# ESP32boardforCNCFTDI.net
KiCad netlist of a schematic drawn in EAGLE
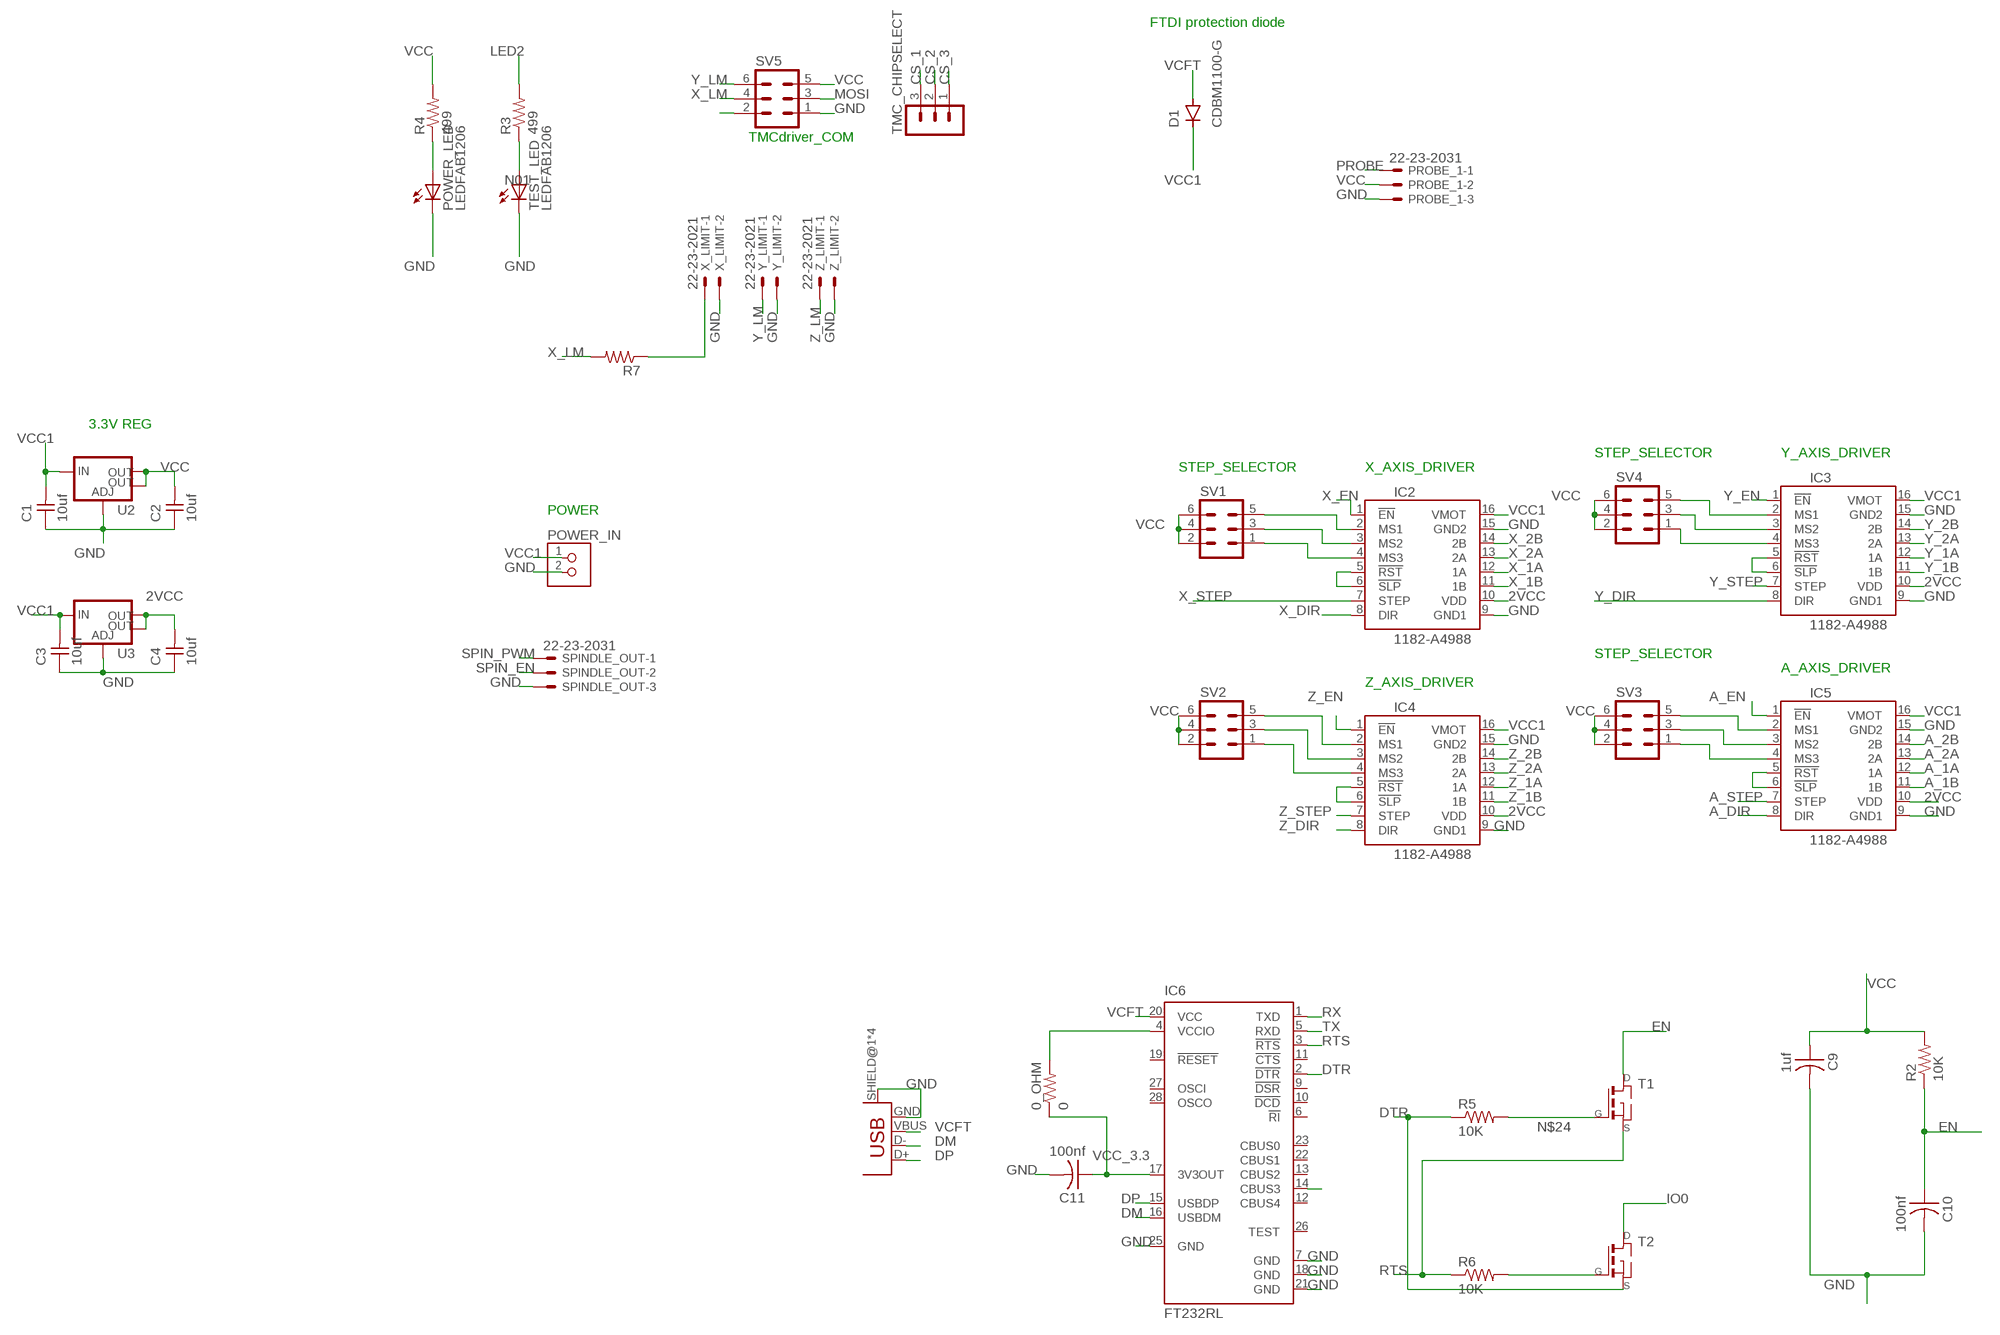
[diagram p0: schematic, sheet 1, part 1 of 2]
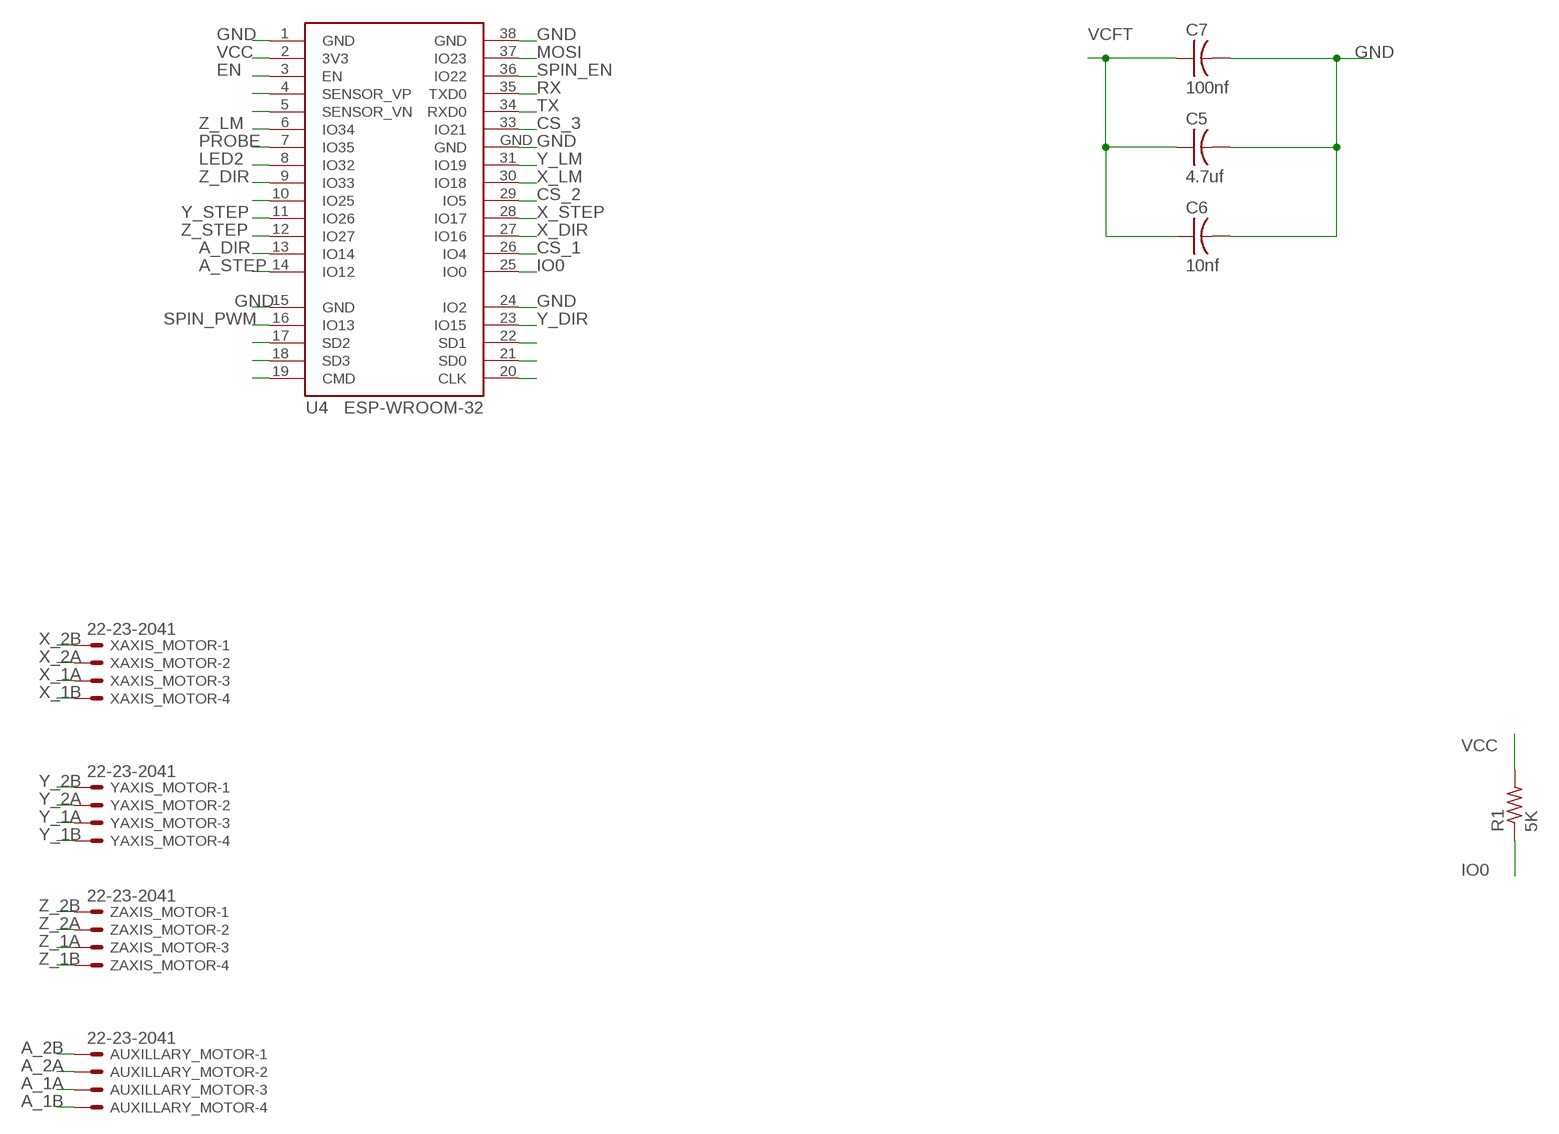
[diagram p1: schematic, sheet 1, part 2 of 2]

(export (version "E")
  (design (tool "Eeschema 10.0.6"))
  (components
    (comp (ref "0_OHM")
      (value "0")
      (footprint "eagle-import:R1206FAB")
      (libsource (lib "eagle-import") (part "fab_22728318_RES-US1206FAB"))
    )
    (comp (ref "AUXILLARY_MOTOR")
      (value "22-23-2041")
      (footprint "eagle-import:22-23-2041")
      (fields (field (name "MF") "MOLEX"))
      (libsource (lib "eagle-import") (part "22-23-2041"))
    )
    (comp (ref "C1")
      (value "10uf")
      (footprint "eagle-import:C1206FAB")
      (libsource (lib "eagle-import") (part "CAP-UNPOLARIZEDFAB"))
    )
    (comp (ref "C2")
      (value "10uf")
      (footprint "eagle-import:C1206FAB")
      (libsource (lib "eagle-import") (part "CAP-UNPOLARIZEDFAB"))
    )
    (comp (ref "C3")
      (value "10uf")
      (footprint "eagle-import:C1206FAB")
      (libsource (lib "eagle-import") (part "CAP-UNPOLARIZEDFAB"))
    )
    (comp (ref "C4")
      (value "10uf")
      (footprint "eagle-import:C1206FAB")
      (libsource (lib "eagle-import") (part "CAP-UNPOLARIZEDFAB"))
    )
    (comp (ref "C5")
      (value "4.7uf")
      (footprint "eagle-import:C1206FAB")
      (libsource (lib "eagle-import") (part "CAP-US1206FAB"))
    )
    (comp (ref "C6")
      (value "10nf")
      (footprint "eagle-import:C1206FAB")
      (libsource (lib "eagle-import") (part "CAP-US1206FAB"))
    )
    (comp (ref "C7")
      (value "100nf")
      (footprint "eagle-import:C1206FAB")
      (libsource (lib "eagle-import") (part "CAP-US1206FAB"))
    )
    (comp (ref "C9")
      (value "1uf")
      (footprint "eagle-import:C1206FAB")
      (libsource (lib "eagle-import") (part "CAP-US1206FAB"))
    )
    (comp (ref "C10")
      (value "100nf")
      (footprint "eagle-import:C1206FAB")
      (libsource (lib "eagle-import") (part "CAP-US1206FAB"))
    )
    (comp (ref "C11")
      (value "100nf")
      (footprint "eagle-import:C1206FAB")
      (libsource (lib "eagle-import") (part "CAP-US1206FAB"))
    )
    (comp (ref "D1")
      (value "CDBM1100-G")
      (footprint "eagle-import:MINI-SMA")
      (libsource (lib "eagle-import") (part "CDBM1100-G"))
    )
    (comp (ref "IC2")
      (value "1182-A4988")
      (footprint "eagle-import:A4988")
      (libsource (lib "eagle-import") (part "1182-A4988"))
    )
    (comp (ref "IC3")
      (value "1182-A4988")
      (footprint "eagle-import:A4988")
      (libsource (lib "eagle-import") (part "1182-A4988"))
    )
    (comp (ref "IC4")
      (value "1182-A4988")
      (footprint "eagle-import:A4988")
      (libsource (lib "eagle-import") (part "1182-A4988"))
    )
    (comp (ref "IC5")
      (value "1182-A4988")
      (footprint "eagle-import:A4988")
      (libsource (lib "eagle-import") (part "1182-A4988"))
    )
    (comp (ref "IC6")
      (value "FT232RL")
      (footprint "eagle-import:SSOP28")
      (libsource (lib "eagle-import") (part "FT232RL"))
    )
    (comp (ref "POWER_IN")
      (value "TERM-1X02-ADAFRUIT")
      (footprint "eagle-import:3.5MMTERM")
      (libsource (lib "eagle-import") (part "TERM-1X02-ADAFRUIT"))
    )
    (comp (ref "POWER_LED")
      (value "LEDFAB1206")
      (footprint "eagle-import:LED1206FAB")
      (libsource (lib "eagle-import") (part "LEDFAB1206"))
    )
    (comp (ref "PROBE_1")
      (value "22-23-2031")
      (footprint "eagle-import:22-23-2031")
      (fields (field (name "MF") "MOLEX"))
      (libsource (lib "eagle-import") (part "22-23-2031"))
    )
    (comp (ref "R1")
      (value "5K")
      (footprint "eagle-import:R1206FAB")
      (libsource (lib "eagle-import") (part "fab_22728318_RES-US1206FAB"))
    )
    (comp (ref "R2")
      (value "10K")
      (footprint "eagle-import:R1206FAB")
      (libsource (lib "eagle-import") (part "fab_22728318_RES-US1206FAB"))
    )
    (comp (ref "R3")
      (value "499")
      (footprint "eagle-import:R1206FAB")
      (libsource (lib "eagle-import") (part "RES-US1206FAB"))
    )
    (comp (ref "R4")
      (value "499")
      (footprint "eagle-import:R1206FAB")
      (libsource (lib "eagle-import") (part "RES-US1206FAB"))
    )
    (comp (ref "R5")
      (value "10K")
      (footprint "eagle-import:R1206FAB")
      (libsource (lib "eagle-import") (part "fab_22728318_RES-US1206FAB"))
    )
    (comp (ref "R6")
      (value "10K")
      (footprint "eagle-import:R1206FAB")
      (libsource (lib "eagle-import") (part "fab_22728318_RES-US1206FAB"))
    )
    (comp (ref "R7")
      (value "RES-US1206FAB")
      (footprint "eagle-import:R1206FAB")
      (libsource (lib "eagle-import") (part "fab_22728318_RES-US1206FAB"))
    )
    (comp (ref "SPINDLE_OUT")
      (value "22-23-2031")
      (footprint "eagle-import:22-23-2031")
      (fields (field (name "MF") "MOLEX"))
      (libsource (lib "eagle-import") (part "22-23-2031"))
    )
    (comp (ref "SV1")
      (value "MA03-2")
      (footprint "eagle-import:MA03-2")
      (libsource (lib "eagle-import") (part "MA03-2"))
    )
    (comp (ref "SV2")
      (value "MA03-2")
      (footprint "eagle-import:MA03-2")
      (libsource (lib "eagle-import") (part "MA03-2"))
    )
    (comp (ref "SV3")
      (value "MA03-2")
      (footprint "eagle-import:MA03-2")
      (libsource (lib "eagle-import") (part "MA03-2"))
    )
    (comp (ref "SV4")
      (value "MA03-2")
      (footprint "eagle-import:MA03-2")
      (libsource (lib "eagle-import") (part "MA03-2"))
    )
    (comp (ref "SV5")
      (value "MA03-2")
      (footprint "eagle-import:MA03-2")
      (libsource (lib "eagle-import") (part "MA03-2"))
    )
    (comp (ref "T1")
      (value "NMOSFETSOT23")
      (footprint "eagle-import:SOT-23")
      (libsource (lib "eagle-import") (part "NMOSFETSOT23"))
    )
    (comp (ref "T2")
      (value "NMOSFETSOT23")
      (footprint "eagle-import:SOT-23")
      (libsource (lib "eagle-import") (part "NMOSFETSOT23"))
    )
    (comp (ref "TEST_LED")
      (value "LEDFAB1206")
      (footprint "eagle-import:LED1206FAB")
      (libsource (lib "eagle-import") (part "LEDFAB1206"))
    )
    (comp (ref "TMC_CHIPSELECT")
      (value "MA03-1")
      (footprint "eagle-import:MA03-1")
      (libsource (lib "eagle-import") (part "MA03-1"))
    )
    (comp (ref "U$1")
      (value "USB_MINIB")
      (footprint "eagle-import:USB_MINIB")
      (libsource (lib "eagle-import") (part "USB_MINIB"))
    )
    (comp (ref "U2")
      (value "V_REG_LM1117SOT223")
      (footprint "eagle-import:SOT223")
      (libsource (lib "eagle-import") (part "V_REG_LM1117SOT223"))
    )
    (comp (ref "U3")
      (value "V_REG_LM1117SOT223")
      (footprint "eagle-import:SOT223")
      (libsource (lib "eagle-import") (part "V_REG_LM1117SOT223"))
    )
    (comp (ref "U4")
      (value "ESP-WROOM-32")
      (footprint "eagle-import:ESP-WROOM-32")
      (libsource (lib "eagle-import") (part "ESP-WROOM-32"))
    )
    (comp (ref "XAXIS_MOTOR")
      (value "22-23-2041")
      (footprint "eagle-import:22-23-2041")
      (fields (field (name "MF") "MOLEX"))
      (libsource (lib "eagle-import") (part "22-23-2041"))
    )
    (comp (ref "X_LIMIT")
      (value "22-23-2021")
      (footprint "eagle-import:22-23-2021")
      (fields (field (name "MF") "MOLEX"))
      (libsource (lib "eagle-import") (part "22-23-2021"))
    )
    (comp (ref "YAXIS_MOTOR")
      (value "22-23-2041")
      (footprint "eagle-import:22-23-2041")
      (fields (field (name "MF") "MOLEX"))
      (libsource (lib "eagle-import") (part "22-23-2041"))
    )
    (comp (ref "Y_LIMIT")
      (value "22-23-2021")
      (footprint "eagle-import:22-23-2021")
      (fields (field (name "MF") "MOLEX"))
      (libsource (lib "eagle-import") (part "22-23-2021"))
    )
    (comp (ref "ZAXIS_MOTOR")
      (value "22-23-2041")
      (footprint "eagle-import:22-23-2041")
      (fields (field (name "MF") "MOLEX"))
      (libsource (lib "eagle-import") (part "22-23-2041"))
    )
    (comp (ref "Z_LIMIT")
      (value "22-23-2021")
      (footprint "eagle-import:22-23-2021")
      (fields (field (name "MF") "MOLEX"))
      (libsource (lib "eagle-import") (part "22-23-2021"))
    )
  )
  (nets
    (net (code "1") (name "/2VCC") (class "Default")
      (node (ref "C4") (pin "2") (pinfunction "2_2") (pintype "passive"))
      (node (ref "IC2") (pin "10") (pinfunction "VDD_10") (pintype "power_in"))
      (node (ref "IC3") (pin "10") (pinfunction "VDD_10") (pintype "power_in"))
      (node (ref "IC4") (pin "10") (pinfunction "VDD_10") (pintype "power_in"))
      (node (ref "IC5") (pin "10") (pinfunction "VDD_10") (pintype "power_in"))
      (node (ref "U3") (pin "2") (pinfunction "OUT_2") (pintype "output"))
      (node (ref "U3") (pin "4") (pinfunction "OUT_4") (pintype "output"))
    )
    (net (code "2") (name "/A_1A") (class "Default")
      (node (ref "AUXILLARY_MOTOR") (pin "3") (pinfunction "S_3") (pintype "passive"))
      (node (ref "IC5") (pin "12") (pinfunction "1A_12") (pintype "output"))
    )
    (net (code "3") (name "/A_1B") (class "Default")
      (node (ref "AUXILLARY_MOTOR") (pin "4") (pinfunction "S_4") (pintype "passive"))
      (node (ref "IC5") (pin "11") (pinfunction "1B_11") (pintype "output"))
    )
    (net (code "4") (name "/A_2A") (class "Default")
      (node (ref "AUXILLARY_MOTOR") (pin "2") (pinfunction "S_2") (pintype "passive"))
      (node (ref "IC5") (pin "13") (pinfunction "2A_13") (pintype "output"))
    )
    (net (code "5") (name "/A_2B") (class "Default")
      (node (ref "AUXILLARY_MOTOR") (pin "1") (pinfunction "S_1") (pintype "passive"))
      (node (ref "IC5") (pin "14") (pinfunction "2B_14") (pintype "output"))
    )
    (net (code "6") (name "/A_DIR") (class "Default")
      (node (ref "IC5") (pin "8") (pinfunction "DIR_8") (pintype "input"))
      (node (ref "U4") (pin "13") (pinfunction "IO14_13") (pintype "bidirectional"))
    )
    (net (code "7") (name "/A_EN") (class "Default")
      (node (ref "IC5") (pin "1") (pinfunction "~{EN}_1") (pintype "passive"))
    )
    (net (code "8") (name "/A_STEP") (class "Default")
      (node (ref "IC5") (pin "7") (pinfunction "STEP_7") (pintype "input"))
      (node (ref "U4") (pin "14") (pinfunction "IO12_14") (pintype "bidirectional"))
    )
    (net (code "9") (name "/CS_1") (class "Default")
      (node (ref "TMC_CHIPSELECT") (pin "3") (pinfunction "3_3") (pintype "passive"))
      (node (ref "U4") (pin "26") (pinfunction "IO4_26") (pintype "bidirectional"))
    )
    (net (code "10") (name "/CS_2") (class "Default")
      (node (ref "TMC_CHIPSELECT") (pin "2") (pinfunction "2_2") (pintype "passive"))
      (node (ref "U4") (pin "29") (pinfunction "IO5_29") (pintype "bidirectional"))
    )
    (net (code "11") (name "/CS_3") (class "Default")
      (node (ref "TMC_CHIPSELECT") (pin "1") (pinfunction "1_1") (pintype "passive"))
      (node (ref "U4") (pin "33") (pinfunction "IO21_33") (pintype "bidirectional"))
    )
    (net (code "12") (name "/DM") (class "Default")
      (node (ref "IC6") (pin "16") (pinfunction "USBDM_16") (pintype "bidirectional"))
      (node (ref "U$1") (pin "D-") (pinfunction "D-_D-") (pintype "bidirectional"))
    )
    (net (code "13") (name "/DP") (class "Default")
      (node (ref "IC6") (pin "15") (pinfunction "USBDP_15") (pintype "bidirectional"))
      (node (ref "U$1") (pin "D+") (pinfunction "D+_D+") (pintype "bidirectional"))
    )
    (net (code "14") (name "/DTR") (class "Default")
      (node (ref "IC6") (pin "2") (pinfunction "~{DTR}_2") (pintype "output"))
      (node (ref "R5") (pin "1") (pinfunction "1_1") (pintype "passive"))
      (node (ref "T2") (pin "2") (pinfunction "S_2") (pintype "passive"))
    )
    (net (code "15") (name "/EN") (class "Default")
      (node (ref "C10") (pin "1") (pinfunction "1_1") (pintype "passive"))
      (node (ref "R2") (pin "1") (pinfunction "1_1") (pintype "passive"))
      (node (ref "T1") (pin "1") (pinfunction "D_1") (pintype "passive"))
      (node (ref "U4") (pin "3") (pinfunction "EN_3") (pintype "input"))
    )
    (net (code "16") (name "/GND") (class "Default")
      (node (ref "C1") (pin "1") (pinfunction "1_1") (pintype "passive"))
      (node (ref "C10") (pin "2") (pinfunction "2_2") (pintype "passive"))
      (node (ref "C11") (pin "2") (pinfunction "2_2") (pintype "passive"))
      (node (ref "C2") (pin "1") (pinfunction "1_1") (pintype "passive"))
      (node (ref "C3") (pin "1") (pinfunction "1_1") (pintype "passive"))
      (node (ref "C4") (pin "1") (pinfunction "1_1") (pintype "passive"))
      (node (ref "C5") (pin "2") (pinfunction "2_2") (pintype "passive"))
      (node (ref "C6") (pin "2") (pinfunction "2_2") (pintype "passive"))
      (node (ref "C7") (pin "2") (pinfunction "2_2") (pintype "passive"))
      (node (ref "C9") (pin "2") (pinfunction "2_2") (pintype "passive"))
      (node (ref "IC2") (pin "15") (pinfunction "GND2_15") (pintype "power_in"))
      (node (ref "IC2") (pin "9") (pinfunction "GND1_9") (pintype "power_in"))
      (node (ref "IC3") (pin "15") (pinfunction "GND2_15") (pintype "power_in"))
      (node (ref "IC3") (pin "9") (pinfunction "GND1_9") (pintype "power_in"))
      (node (ref "IC4") (pin "15") (pinfunction "GND2_15") (pintype "power_in"))
      (node (ref "IC4") (pin "9") (pinfunction "GND1_9") (pintype "power_in"))
      (node (ref "IC5") (pin "15") (pinfunction "GND2_15") (pintype "power_in"))
      (node (ref "IC5") (pin "9") (pinfunction "GND1_9") (pintype "power_in"))
      (node (ref "IC6") (pin "18") (pinfunction "GND_18") (pintype "power_in"))
      (node (ref "IC6") (pin "21") (pinfunction "GND_21") (pintype "power_in"))
      (node (ref "IC6") (pin "25") (pinfunction "GND_25") (pintype "power_in"))
      (node (ref "IC6") (pin "7") (pinfunction "GND_7") (pintype "power_in"))
      (node (ref "POWER_IN") (pin "2") (pinfunction "2_2") (pintype "passive"))
      (node (ref "POWER_LED") (pin "2") (pinfunction "C_2") (pintype "passive"))
      (node (ref "PROBE_1") (pin "3") (pinfunction "S_3") (pintype "passive"))
      (node (ref "SPINDLE_OUT") (pin "3") (pinfunction "S_3") (pintype "passive"))
      (node (ref "SV5") (pin "1") (pinfunction "1_1") (pintype "passive"))
      (node (ref "TEST_LED") (pin "2") (pinfunction "C_2") (pintype "passive"))
      (node (ref "U$1") (pin "GND") (pinfunction "GND_GND") (pintype "bidirectional"))
      (node (ref "U$1") (pin "SHIELD@1") (pinfunction "SHIELD_SHIELD@1") (pintype "passive"))
      (node (ref "U$1") (pin "SHIELD@2") (pinfunction "SHIELD_SHIELD@2") (pintype "passive"))
      (node (ref "U$1") (pin "SHIELD@3") (pinfunction "SHIELD_SHIELD@3") (pintype "passive"))
      (node (ref "U$1") (pin "SHIELD@4") (pinfunction "SHIELD_SHIELD@4") (pintype "passive"))
      (node (ref "U2") (pin "1") (pinfunction "ADJ_1") (pintype "input"))
      (node (ref "U3") (pin "1") (pinfunction "ADJ_1") (pintype "input"))
      (node (ref "U4") (pin "1") (pinfunction "GND_1") (pintype "power_in"))
      (node (ref "U4") (pin "15") (pinfunction "GND_15") (pintype "power_in"))
      (node (ref "U4") (pin "24") (pinfunction "IO2_24") (pintype "bidirectional"))
      (node (ref "U4") (pin "38") (pinfunction "GND_38") (pintype "power_in"))
      (node (ref "U4") (pin "GND") (pinfunction "GND_GND") (pintype "power_in"))
      (node (ref "X_LIMIT") (pin "2") (pinfunction "S_2") (pintype "passive"))
      (node (ref "Y_LIMIT") (pin "2") (pinfunction "S_2") (pintype "passive"))
      (node (ref "Z_LIMIT") (pin "2") (pinfunction "S_2") (pintype "passive"))
    )
    (net (code "17") (name "/IO0") (class "Default")
      (node (ref "R1") (pin "1") (pinfunction "1_1") (pintype "passive"))
      (node (ref "T2") (pin "1") (pinfunction "D_1") (pintype "passive"))
      (node (ref "U4") (pin "25") (pinfunction "IO0_25") (pintype "bidirectional"))
    )
    (net (code "18") (name "/LED2") (class "Default")
      (node (ref "R3") (pin "2") (pinfunction "2_2") (pintype "passive"))
      (node (ref "U4") (pin "8") (pinfunction "IO32_8") (pintype "bidirectional"))
    )
    (net (code "19") (name "/MOSI") (class "Default")
      (node (ref "SV5") (pin "3") (pinfunction "3_3") (pintype "passive"))
      (node (ref "U4") (pin "37") (pinfunction "IO23_37") (pintype "bidirectional"))
    )
    (net (code "20") (name "/N$24") (class "Default")
      (node (ref "R5") (pin "2") (pinfunction "2_2") (pintype "passive"))
      (node (ref "T1") (pin "3") (pinfunction "G_3") (pintype "passive"))
    )
    (net (code "21") (name "/N01") (class "Default")
      (node (ref "R3") (pin "1") (pinfunction "1_1") (pintype "passive"))
      (node (ref "TEST_LED") (pin "1") (pinfunction "A_1") (pintype "passive"))
    )
    (net (code "22") (name "/PROBE") (class "Default")
      (node (ref "PROBE_1") (pin "1") (pinfunction "S_1") (pintype "passive"))
      (node (ref "U4") (pin "7") (pinfunction "IO35_7") (pintype "bidirectional"))
    )
    (net (code "23") (name "/RTS") (class "Default")
      (node (ref "IC6") (pin "3") (pinfunction "~{RTS}_3") (pintype "output"))
      (node (ref "R6") (pin "1") (pinfunction "1_1") (pintype "passive"))
      (node (ref "T1") (pin "2") (pinfunction "S_2") (pintype "passive"))
    )
    (net (code "24") (name "/RX") (class "Default")
      (node (ref "IC6") (pin "1") (pinfunction "TXD_1") (pintype "output"))
      (node (ref "U4") (pin "35") (pinfunction "TXD0_35") (pintype "bidirectional"))
    )
    (net (code "25") (name "/SPIN_EN") (class "Default")
      (node (ref "SPINDLE_OUT") (pin "2") (pinfunction "S_2") (pintype "passive"))
      (node (ref "U4") (pin "36") (pinfunction "IO22_36") (pintype "bidirectional"))
    )
    (net (code "26") (name "/SPIN_PWM") (class "Default")
      (node (ref "SPINDLE_OUT") (pin "1") (pinfunction "S_1") (pintype "passive"))
      (node (ref "U4") (pin "16") (pinfunction "IO13_16") (pintype "bidirectional"))
    )
    (net (code "27") (name "/TX") (class "Default")
      (node (ref "IC6") (pin "5") (pinfunction "RXD_5") (pintype "input"))
      (node (ref "U4") (pin "34") (pinfunction "RXD0_34") (pintype "bidirectional"))
    )
    (net (code "28") (name "/VCC") (class "Default")
      (node (ref "C2") (pin "2") (pinfunction "2_2") (pintype "passive"))
      (node (ref "C9") (pin "1") (pinfunction "1_1") (pintype "passive"))
      (node (ref "PROBE_1") (pin "2") (pinfunction "S_2") (pintype "passive"))
      (node (ref "R1") (pin "2") (pinfunction "2_2") (pintype "passive"))
      (node (ref "R2") (pin "2") (pinfunction "2_2") (pintype "passive"))
      (node (ref "R4") (pin "2") (pinfunction "2_2") (pintype "passive"))
      (node (ref "SV1") (pin "2") (pinfunction "2_2") (pintype "passive"))
      (node (ref "SV1") (pin "4") (pinfunction "4_4") (pintype "passive"))
      (node (ref "SV1") (pin "6") (pinfunction "6_6") (pintype "passive"))
      (node (ref "SV2") (pin "2") (pinfunction "2_2") (pintype "passive"))
      (node (ref "SV2") (pin "4") (pinfunction "4_4") (pintype "passive"))
      (node (ref "SV2") (pin "6") (pinfunction "6_6") (pintype "passive"))
      (node (ref "SV3") (pin "2") (pinfunction "2_2") (pintype "passive"))
      (node (ref "SV3") (pin "4") (pinfunction "4_4") (pintype "passive"))
      (node (ref "SV3") (pin "6") (pinfunction "6_6") (pintype "passive"))
      (node (ref "SV4") (pin "2") (pinfunction "2_2") (pintype "passive"))
      (node (ref "SV4") (pin "4") (pinfunction "4_4") (pintype "passive"))
      (node (ref "SV4") (pin "6") (pinfunction "6_6") (pintype "passive"))
      (node (ref "SV5") (pin "5") (pinfunction "5_5") (pintype "passive"))
      (node (ref "U2") (pin "2") (pinfunction "OUT_2") (pintype "output"))
      (node (ref "U2") (pin "4") (pinfunction "OUT_4") (pintype "output"))
      (node (ref "U4") (pin "2") (pinfunction "3V3_2") (pintype "power_in"))
    )
    (net (code "29") (name "/VCC1") (class "Default")
      (node (ref "C1") (pin "2") (pinfunction "2_2") (pintype "passive"))
      (node (ref "C3") (pin "2") (pinfunction "2_2") (pintype "passive"))
      (node (ref "D1") (pin "KATHODE") (pinfunction "KATHODE_KATHODE") (pintype "bidirectional"))
      (node (ref "IC2") (pin "16") (pinfunction "VMOT_16") (pintype "power_in"))
      (node (ref "IC3") (pin "16") (pinfunction "VMOT_16") (pintype "power_in"))
      (node (ref "IC4") (pin "16") (pinfunction "VMOT_16") (pintype "power_in"))
      (node (ref "IC5") (pin "16") (pinfunction "VMOT_16") (pintype "power_in"))
      (node (ref "POWER_IN") (pin "1") (pinfunction "1_1") (pintype "passive"))
      (node (ref "U2") (pin "3") (pinfunction "IN_3") (pintype "input"))
      (node (ref "U3") (pin "3") (pinfunction "IN_3") (pintype "input"))
    )
    (net (code "30") (name "/VCC_3.3") (class "Default")
      (node (ref "0_OHM") (pin "1") (pinfunction "1_1") (pintype "passive"))
      (node (ref "C11") (pin "1") (pinfunction "1_1") (pintype "passive"))
      (node (ref "IC6") (pin "17") (pinfunction "3V3OUT_17") (pintype "output"))
    )
    (net (code "31") (name "/VCFT") (class "Default")
      (node (ref "C5") (pin "1") (pinfunction "1_1") (pintype "passive"))
      (node (ref "C6") (pin "1") (pinfunction "1_1") (pintype "passive"))
      (node (ref "C7") (pin "1") (pinfunction "1_1") (pintype "passive"))
      (node (ref "D1") (pin "ANODE") (pinfunction "ANODE_ANODE") (pintype "bidirectional"))
      (node (ref "IC6") (pin "20") (pinfunction "VCC_20") (pintype "power_in"))
      (node (ref "U$1") (pin "VBUS") (pinfunction "VBUS_VBUS") (pintype "bidirectional"))
    )
    (net (code "32") (name "/X_1A") (class "Default")
      (node (ref "IC2") (pin "12") (pinfunction "1A_12") (pintype "output"))
      (node (ref "XAXIS_MOTOR") (pin "3") (pinfunction "S_3") (pintype "passive"))
    )
    (net (code "33") (name "/X_1B") (class "Default")
      (node (ref "IC2") (pin "11") (pinfunction "1B_11") (pintype "output"))
      (node (ref "XAXIS_MOTOR") (pin "4") (pinfunction "S_4") (pintype "passive"))
    )
    (net (code "34") (name "/X_2A") (class "Default")
      (node (ref "IC2") (pin "13") (pinfunction "2A_13") (pintype "output"))
      (node (ref "XAXIS_MOTOR") (pin "2") (pinfunction "S_2") (pintype "passive"))
    )
    (net (code "35") (name "/X_2B") (class "Default")
      (node (ref "IC2") (pin "14") (pinfunction "2B_14") (pintype "output"))
      (node (ref "XAXIS_MOTOR") (pin "1") (pinfunction "S_1") (pintype "passive"))
    )
    (net (code "36") (name "/X_DIR") (class "Default")
      (node (ref "IC2") (pin "8") (pinfunction "DIR_8") (pintype "input"))
      (node (ref "U4") (pin "27") (pinfunction "IO16_27") (pintype "bidirectional"))
    )
    (net (code "37") (name "/X_EN") (class "Default")
      (node (ref "IC2") (pin "1") (pinfunction "~{EN}_1") (pintype "passive"))
    )
    (net (code "38") (name "/X_LM") (class "Default")
      (node (ref "R7") (pin "2") (pinfunction "2_2") (pintype "passive"))
      (node (ref "SV5") (pin "4") (pinfunction "4_4") (pintype "passive"))
      (node (ref "U4") (pin "30") (pinfunction "IO18_30") (pintype "bidirectional"))
    )
    (net (code "39") (name "/X_STEP") (class "Default")
      (node (ref "IC2") (pin "7") (pinfunction "STEP_7") (pintype "input"))
      (node (ref "U4") (pin "28") (pinfunction "IO17_28") (pintype "bidirectional"))
    )
    (net (code "40") (name "/Y_1A") (class "Default")
      (node (ref "IC3") (pin "12") (pinfunction "1A_12") (pintype "output"))
      (node (ref "YAXIS_MOTOR") (pin "3") (pinfunction "S_3") (pintype "passive"))
    )
    (net (code "41") (name "/Y_1B") (class "Default")
      (node (ref "IC3") (pin "11") (pinfunction "1B_11") (pintype "output"))
      (node (ref "YAXIS_MOTOR") (pin "4") (pinfunction "S_4") (pintype "passive"))
    )
    (net (code "42") (name "/Y_2A") (class "Default")
      (node (ref "IC3") (pin "13") (pinfunction "2A_13") (pintype "output"))
      (node (ref "YAXIS_MOTOR") (pin "2") (pinfunction "S_2") (pintype "passive"))
    )
    (net (code "43") (name "/Y_2B") (class "Default")
      (node (ref "IC3") (pin "14") (pinfunction "2B_14") (pintype "output"))
      (node (ref "YAXIS_MOTOR") (pin "1") (pinfunction "S_1") (pintype "passive"))
    )
    (net (code "44") (name "/Y_DIR") (class "Default")
      (node (ref "IC3") (pin "8") (pinfunction "DIR_8") (pintype "input"))
      (node (ref "U4") (pin "23") (pinfunction "IO15_23") (pintype "bidirectional"))
    )
    (net (code "45") (name "/Y_EN") (class "Default")
      (node (ref "IC3") (pin "1") (pinfunction "~{EN}_1") (pintype "passive"))
    )
    (net (code "46") (name "/Y_LM") (class "Default")
      (node (ref "SV5") (pin "6") (pinfunction "6_6") (pintype "passive"))
      (node (ref "U4") (pin "31") (pinfunction "IO19_31") (pintype "bidirectional"))
      (node (ref "Y_LIMIT") (pin "1") (pinfunction "S_1") (pintype "passive"))
    )
    (net (code "47") (name "/Y_STEP") (class "Default")
      (node (ref "IC3") (pin "7") (pinfunction "STEP_7") (pintype "input"))
      (node (ref "U4") (pin "11") (pinfunction "IO26_11") (pintype "bidirectional"))
    )
    (net (code "48") (name "/Z_1A") (class "Default")
      (node (ref "IC4") (pin "12") (pinfunction "1A_12") (pintype "output"))
      (node (ref "ZAXIS_MOTOR") (pin "3") (pinfunction "S_3") (pintype "passive"))
    )
    (net (code "49") (name "/Z_1B") (class "Default")
      (node (ref "IC4") (pin "11") (pinfunction "1B_11") (pintype "output"))
      (node (ref "ZAXIS_MOTOR") (pin "4") (pinfunction "S_4") (pintype "passive"))
    )
    (net (code "50") (name "/Z_2A") (class "Default")
      (node (ref "IC4") (pin "13") (pinfunction "2A_13") (pintype "output"))
      (node (ref "ZAXIS_MOTOR") (pin "2") (pinfunction "S_2") (pintype "passive"))
    )
    (net (code "51") (name "/Z_2B") (class "Default")
      (node (ref "IC4") (pin "14") (pinfunction "2B_14") (pintype "output"))
      (node (ref "ZAXIS_MOTOR") (pin "1") (pinfunction "S_1") (pintype "passive"))
    )
    (net (code "52") (name "/Z_DIR") (class "Default")
      (node (ref "IC4") (pin "8") (pinfunction "DIR_8") (pintype "input"))
      (node (ref "U4") (pin "9") (pinfunction "IO33_9") (pintype "bidirectional"))
    )
    (net (code "53") (name "/Z_EN") (class "Default")
      (node (ref "IC4") (pin "1") (pinfunction "~{EN}_1") (pintype "passive"))
    )
    (net (code "54") (name "/Z_LM") (class "Default")
      (node (ref "U4") (pin "6") (pinfunction "IO34_6") (pintype "bidirectional"))
      (node (ref "Z_LIMIT") (pin "1") (pinfunction "S_1") (pintype "passive"))
    )
    (net (code "55") (name "/Z_STEP") (class "Default")
      (node (ref "IC4") (pin "7") (pinfunction "STEP_7") (pintype "input"))
      (node (ref "U4") (pin "12") (pinfunction "IO27_12") (pintype "bidirectional"))
    )
    (net (code "56") (name "Net-(IC2-MS1)") (class "Default")
      (node (ref "IC2") (pin "2") (pinfunction "MS1_2") (pintype "passive"))
      (node (ref "SV1") (pin "5") (pinfunction "5_5") (pintype "passive"))
    )
    (net (code "57") (name "Net-(IC2-MS2)") (class "Default")
      (node (ref "IC2") (pin "3") (pinfunction "MS2_3") (pintype "passive"))
      (node (ref "SV1") (pin "3") (pinfunction "3_3") (pintype "passive"))
    )
    (net (code "58") (name "Net-(IC2-MS3)") (class "Default")
      (node (ref "IC2") (pin "4") (pinfunction "MS3_4") (pintype "passive"))
      (node (ref "SV1") (pin "1") (pinfunction "1_1") (pintype "passive"))
    )
    (net (code "59") (name "Net-(IC2-~{RST})") (class "Default")
      (node (ref "IC2") (pin "5") (pinfunction "~{RST}_5") (pintype "passive"))
      (node (ref "IC2") (pin "6") (pinfunction "~{SLP}_6") (pintype "passive"))
    )
    (net (code "60") (name "Net-(IC3-MS1)") (class "Default")
      (node (ref "IC3") (pin "2") (pinfunction "MS1_2") (pintype "passive"))
      (node (ref "SV4") (pin "5") (pinfunction "5_5") (pintype "passive"))
    )
    (net (code "61") (name "Net-(IC3-MS2)") (class "Default")
      (node (ref "IC3") (pin "3") (pinfunction "MS2_3") (pintype "passive"))
      (node (ref "SV4") (pin "3") (pinfunction "3_3") (pintype "passive"))
    )
    (net (code "62") (name "Net-(IC3-MS3)") (class "Default")
      (node (ref "IC3") (pin "4") (pinfunction "MS3_4") (pintype "passive"))
      (node (ref "SV4") (pin "1") (pinfunction "1_1") (pintype "passive"))
    )
    (net (code "63") (name "Net-(IC3-~{RST})") (class "Default")
      (node (ref "IC3") (pin "5") (pinfunction "~{RST}_5") (pintype "passive"))
      (node (ref "IC3") (pin "6") (pinfunction "~{SLP}_6") (pintype "passive"))
    )
    (net (code "64") (name "Net-(IC4-MS1)") (class "Default")
      (node (ref "IC4") (pin "2") (pinfunction "MS1_2") (pintype "passive"))
      (node (ref "SV2") (pin "5") (pinfunction "5_5") (pintype "passive"))
    )
    (net (code "65") (name "Net-(IC4-MS2)") (class "Default")
      (node (ref "IC4") (pin "3") (pinfunction "MS2_3") (pintype "passive"))
      (node (ref "SV2") (pin "3") (pinfunction "3_3") (pintype "passive"))
    )
    (net (code "66") (name "Net-(IC4-MS3)") (class "Default")
      (node (ref "IC4") (pin "4") (pinfunction "MS3_4") (pintype "passive"))
      (node (ref "SV2") (pin "1") (pinfunction "1_1") (pintype "passive"))
    )
    (net (code "67") (name "Net-(IC4-~{RST})") (class "Default")
      (node (ref "IC4") (pin "5") (pinfunction "~{RST}_5") (pintype "passive"))
      (node (ref "IC4") (pin "6") (pinfunction "~{SLP}_6") (pintype "passive"))
    )
    (net (code "68") (name "Net-(IC5-MS1)") (class "Default")
      (node (ref "IC5") (pin "2") (pinfunction "MS1_2") (pintype "passive"))
      (node (ref "SV3") (pin "5") (pinfunction "5_5") (pintype "passive"))
    )
    (net (code "69") (name "Net-(IC5-MS2)") (class "Default")
      (node (ref "IC5") (pin "3") (pinfunction "MS2_3") (pintype "passive"))
      (node (ref "SV3") (pin "3") (pinfunction "3_3") (pintype "passive"))
    )
    (net (code "70") (name "Net-(IC5-MS3)") (class "Default")
      (node (ref "IC5") (pin "4") (pinfunction "MS3_4") (pintype "passive"))
      (node (ref "SV3") (pin "1") (pinfunction "1_1") (pintype "passive"))
    )
    (net (code "71") (name "Net-(IC5-~{RST})") (class "Default")
      (node (ref "IC5") (pin "5") (pinfunction "~{RST}_5") (pintype "passive"))
      (node (ref "IC5") (pin "6") (pinfunction "~{SLP}_6") (pintype "passive"))
    )
    (net (code "72") (name "Net-(IC6-VCCIO)") (class "Default")
      (node (ref "0_OHM") (pin "2") (pinfunction "2_2") (pintype "passive"))
      (node (ref "IC6") (pin "4") (pinfunction "VCCIO_4") (pintype "power_in"))
    )
    (net (code "73") (name "Net-(POWER_LED-A)") (class "Default")
      (node (ref "POWER_LED") (pin "1") (pinfunction "A_1") (pintype "passive"))
      (node (ref "R4") (pin "1") (pinfunction "1_1") (pintype "passive"))
    )
    (net (code "74") (name "Net-(T2-G)") (class "Default")
      (node (ref "R6") (pin "2") (pinfunction "2_2") (pintype "passive"))
      (node (ref "T2") (pin "3") (pinfunction "G_3") (pintype "passive"))
    )
    (net (code "75") (name "Net-(X_LIMITA-S)") (class "Default")
      (node (ref "R7") (pin "1") (pinfunction "1_1") (pintype "passive"))
      (node (ref "X_LIMIT") (pin "1") (pinfunction "S_1") (pintype "passive"))
    )
    (net (code "76") (name "unconnected-(IC6-CBUS0-Pad23)") (class "Default")
      (node (ref "IC6") (pin "23") (pinfunction "CBUS0_23") (pintype "bidirectional"))
    )
    (net (code "77") (name "unconnected-(IC6-CBUS1-Pad22)") (class "Default")
      (node (ref "IC6") (pin "22") (pinfunction "CBUS1_22") (pintype "bidirectional"))
    )
    (net (code "78") (name "unconnected-(IC6-CBUS2-Pad13)") (class "Default")
      (node (ref "IC6") (pin "13") (pinfunction "CBUS2_13") (pintype "bidirectional"))
    )
    (net (code "79") (name "unconnected-(IC6-CBUS3-Pad14)") (class "Default")
      (node (ref "IC6") (pin "14") (pinfunction "CBUS3_14") (pintype "bidirectional"))
    )
    (net (code "80") (name "unconnected-(IC6-CBUS4-Pad12)") (class "Default")
      (node (ref "IC6") (pin "12") (pinfunction "CBUS4_12") (pintype "bidirectional"))
    )
    (net (code "81") (name "unconnected-(IC6-OSCI-Pad27)") (class "Default")
      (node (ref "IC6") (pin "27") (pinfunction "OSCI_27") (pintype "input"))
    )
    (net (code "82") (name "unconnected-(IC6-OSCO-Pad28)") (class "Default")
      (node (ref "IC6") (pin "28") (pinfunction "OSCO_28") (pintype "output"))
    )
    (net (code "83") (name "unconnected-(IC6-TEST-Pad26)") (class "Default")
      (node (ref "IC6") (pin "26") (pinfunction "TEST_26") (pintype "input"))
    )
    (net (code "84") (name "unconnected-(IC6-~{CTS}-Pad11)") (class "Default")
      (node (ref "IC6") (pin "11") (pinfunction "~{CTS}_11") (pintype "input"))
    )
    (net (code "85") (name "unconnected-(IC6-~{DCD}-Pad10)") (class "Default")
      (node (ref "IC6") (pin "10") (pinfunction "~{DCD}_10") (pintype "input"))
    )
    (net (code "86") (name "unconnected-(IC6-~{DSR}-Pad9)") (class "Default")
      (node (ref "IC6") (pin "9") (pinfunction "~{DSR}_9") (pintype "input"))
    )
    (net (code "87") (name "unconnected-(IC6-~{RESET}-Pad19)") (class "Default")
      (node (ref "IC6") (pin "19") (pinfunction "~{RESET}_19") (pintype "input"))
    )
    (net (code "88") (name "unconnected-(IC6-~{RI}-Pad6)") (class "Default")
      (node (ref "IC6") (pin "6") (pinfunction "~{RI}_6") (pintype "input"))
    )
    (net (code "89") (name "unconnected-(SV5-Pad2)") (class "Default")
      (node (ref "SV5") (pin "2") (pinfunction "2_2") (pintype "passive"))
    )
    (net (code "90") (name "unconnected-(U4-CLK-Pad20)") (class "Default")
      (node (ref "U4") (pin "20") (pinfunction "CLK_20") (pintype "bidirectional"))
    )
    (net (code "91") (name "unconnected-(U4-CMD-Pad19)") (class "Default")
      (node (ref "U4") (pin "19") (pinfunction "CMD_19") (pintype "bidirectional"))
    )
    (net (code "92") (name "unconnected-(U4-IO25-Pad10)") (class "Default")
      (node (ref "U4") (pin "10") (pinfunction "IO25_10") (pintype "bidirectional"))
    )
    (net (code "93") (name "unconnected-(U4-SD0-Pad21)") (class "Default")
      (node (ref "U4") (pin "21") (pinfunction "SD0_21") (pintype "bidirectional"))
    )
    (net (code "94") (name "unconnected-(U4-SD1-Pad22)") (class "Default")
      (node (ref "U4") (pin "22") (pinfunction "SD1_22") (pintype "bidirectional"))
    )
    (net (code "95") (name "unconnected-(U4-SD2-Pad17)") (class "Default")
      (node (ref "U4") (pin "17") (pinfunction "SD2_17") (pintype "bidirectional"))
    )
    (net (code "96") (name "unconnected-(U4-SD3-Pad18)") (class "Default")
      (node (ref "U4") (pin "18") (pinfunction "SD3_18") (pintype "bidirectional"))
    )
    (net (code "97") (name "unconnected-(U4-SENSOR_VN-Pad5)") (class "Default")
      (node (ref "U4") (pin "5") (pinfunction "SENSOR_VN_5") (pintype "bidirectional"))
    )
    (net (code "98") (name "unconnected-(U4-SENSOR_VP-Pad4)") (class "Default")
      (node (ref "U4") (pin "4") (pinfunction "SENSOR_VP_4") (pintype "bidirectional"))
    )
  )
)
